# Audio_Input_Digitial_Mic.net
KiCad netlist of a schematic drawn in Altium Designer
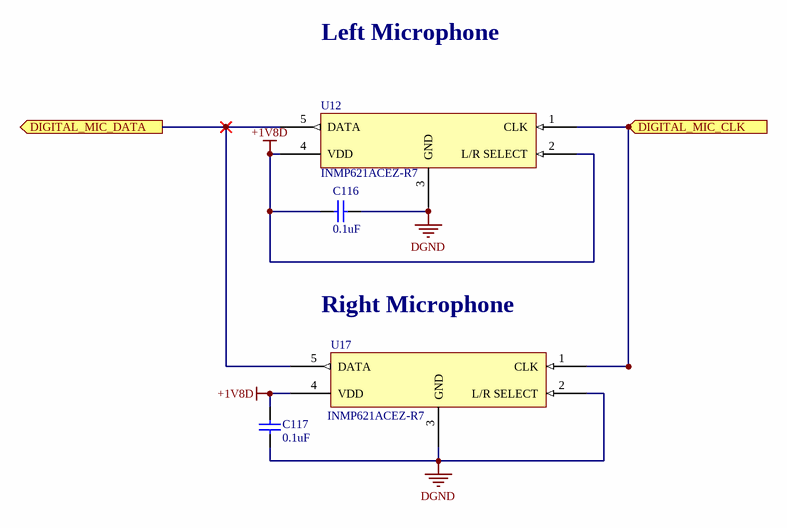
[diagram p0: Audio_Input_Digitial_Mic.SchDoc]

(export (version "E")
  (design (tool "Eeschema 10.0.6"))
  (components
    (comp (ref "C116")
      (value "CL10F104ZO8NNNC")
      (footprint "3-0603_L")
      (description "CAP CER 0.1UF 16V Y5V 0603")
      (fields
        (field (name "MANUFACTURER") "Samsung")
        (field (name "TOLERANCE") "80%")
        (field (name "CAPACITANCE") "0.1uF")
      )
      (libsource (lib "Schematic_Components_CD") (part "CL10F104ZO8NNNC"))
    )
    (comp (ref "C117")
      (value "CL10F104ZO8NNNC")
      (footprint "3-0603_L")
      (description "CAP CER 0.1UF 16V Y5V 0603")
      (fields
        (field (name "MANUFACTURER") "Samsung")
        (field (name "TOLERANCE") "80%")
        (field (name "CAPACITANCE") "0.1uF")
      )
      (libsource (lib "Schematic_Components_CD") (part "CL10F104ZO8NNNC"))
    )
    (comp (ref "U12")
      (value "INMP621")
      (footprint "INMP621")
      (fields
        (field (name "MANUFACTURER") "InvenSense")
        (field (name "MANUFACTURER PART NUMBER") "INMP621ACEZ-R7")
      )
      (libsource (lib "NIH_DE0_Nano_Daughter_Card_Library") (part "INMP621"))
    )
    (comp (ref "U17")
      (value "INMP621")
      (footprint "INMP621")
      (fields
        (field (name "MANUFACTURER") "InvenSense")
        (field (name "MANUFACTURER PART NUMBER") "INMP621ACEZ-R7")
      )
      (libsource (lib "NIH_DE0_Nano_Daughter_Card_Library") (part "INMP621"))
    )
  )
  (nets
    (net (code "1") (name "+1V8D") (class "Default")
      (node (ref "C116") (pin "2") (pinfunction "2_2") (pintype "passive"))
      (node (ref "C117") (pin "1") (pinfunction "1_1") (pintype "passive"))
      (node (ref "U12") (pin "2") (pinfunction "L/R_SELECT_2") (pintype "input"))
      (node (ref "U12") (pin "4") (pinfunction "VDD_4") (pintype "passive"))
      (node (ref "U17") (pin "4") (pinfunction "VDD_4") (pintype "passive"))
    )
    (net (code "2") (name "/DIGITAL_MIC_CLK") (class "Default")
      (node (ref "U12") (pin "1") (pinfunction "CLK_1") (pintype "input"))
      (node (ref "U17") (pin "1") (pinfunction "CLK_1") (pintype "input"))
    )
    (net (code "3") (name "/DIGITAL_MIC_DATA") (class "Default")
      (node (ref "U12") (pin "5") (pinfunction "DATA_5") (pintype "output"))
      (node (ref "U17") (pin "5") (pinfunction "DATA_5") (pintype "output"))
    )
    (net (code "4") (name "DGND") (class "Default")
      (node (ref "C116") (pin "1") (pinfunction "1_1") (pintype "passive"))
      (node (ref "C117") (pin "2") (pinfunction "2_2") (pintype "passive"))
      (node (ref "U12") (pin "3") (pinfunction "GND_3") (pintype "passive"))
      (node (ref "U17") (pin "2") (pinfunction "L/R_SELECT_2") (pintype "input"))
      (node (ref "U17") (pin "3") (pinfunction "GND_3") (pintype "passive"))
    )
  )
)
